# tech_safari_data_logger.net
KiCad netlist of a schematic drawn in EAGLE
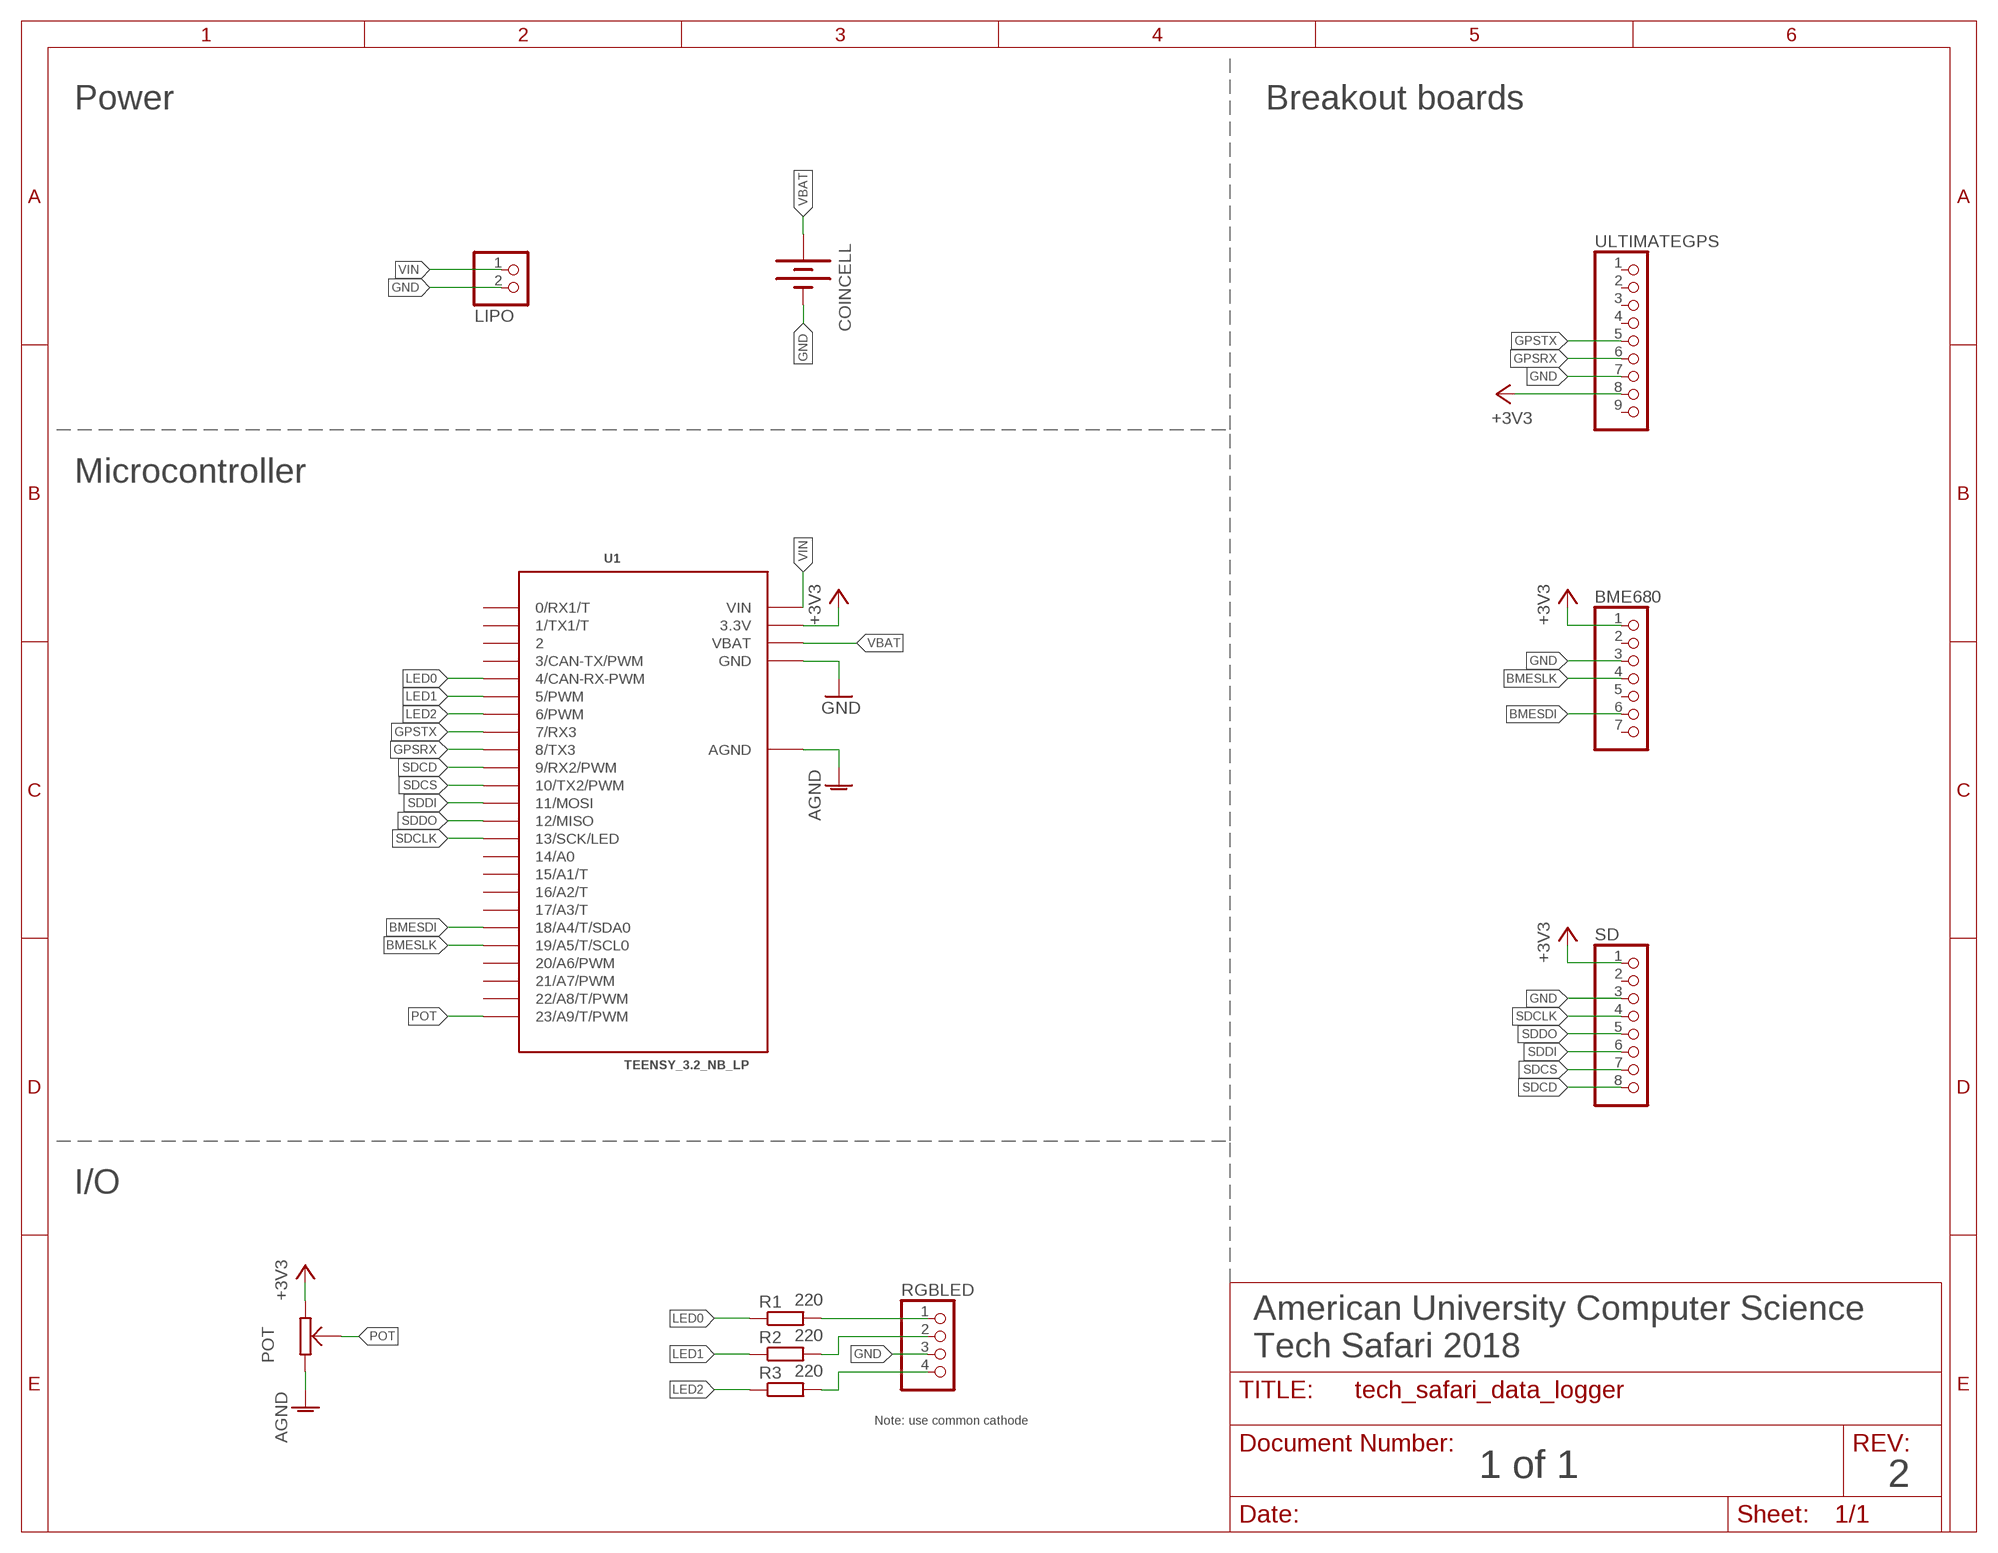
[diagram p0: schematic, sheet 1]

(export (version "E")
  (design (tool "Eeschema 10.0.6"))
  (components
    (comp (ref "BME680")
      (value "PINHD-1X7")
      (footprint "eagle-import:1X07")
      (libsource (lib "eagle-import") (part "PINHD-1X7"))
    )
    (comp (ref "COINCELL")
      (value "BATTERY")
      (footprint "eagle-import:BATTCON_20MM_SMALL")
      (libsource (lib "eagle-import") (part "BATTERY"))
    )
    (comp (ref "LIPO")
      (value "JST_2PIN-THM-RA")
      (footprint "eagle-import:JST-PH-2-THM-RA")
      (libsource (lib "eagle-import") (part "JST_2PIN-THM-RA"))
    )
    (comp (ref "POT")
      (value "POTENTIOMETER_THRU")
      (footprint "eagle-import:POTENTIOMETER_THRU")
      (libsource (lib "eagle-import") (part "POTENTIOMETER_THRU"))
    )
    (comp (ref "R1")
      (value "220")
      (footprint "eagle-import:0207_10")
      (libsource (lib "eagle-import") (part "R-EU_0207/10"))
    )
    (comp (ref "R2")
      (value "220")
      (footprint "eagle-import:0207_10")
      (libsource (lib "eagle-import") (part "R-EU_0207/10"))
    )
    (comp (ref "R3")
      (value "220")
      (footprint "eagle-import:0207_10")
      (libsource (lib "eagle-import") (part "R-EU_0207/10"))
    )
    (comp (ref "RGBLED")
      (value "PINHD-1X4")
      (footprint "eagle-import:1X04")
      (libsource (lib "eagle-import") (part "PINHD-1X4"))
    )
    (comp (ref "SD")
      (value "PINHD-1X8")
      (footprint "eagle-import:1X08")
      (libsource (lib "eagle-import") (part "PINHD-1X8"))
    )
    (comp (ref "U1")
      (value "TEENSY_3.2_NB_LP")
      (footprint "eagle-import:TEENSY_3.2__NB_LP")
      (libsource (lib "eagle-import") (part "TEENSY_3.2_NB_LP"))
    )
    (comp (ref "ULTIMATEGPS")
      (value "PINHD-1X9")
      (footprint "eagle-import:1X09")
      (libsource (lib "eagle-import") (part "PINHD-1X9"))
    )
  )
  (nets
    (net (code "1") (name "+3V3") (class "Default")
      (node (ref "BME680") (pin "1") (pinfunction "1_1") (pintype "passive"))
      (node (ref "POT") (pin "3") (pinfunction "3_3") (pintype "passive"))
      (node (ref "SD") (pin "1") (pinfunction "1_1") (pintype "passive"))
      (node (ref "U1") (pin "3.3V") (pinfunction "3.3V_3.3V") (pintype "power_in"))
      (node (ref "ULTIMATEGPS") (pin "8") (pinfunction "8_8") (pintype "passive"))
    )
    (net (code "2") (name "AGND") (class "Default")
      (node (ref "POT") (pin "1") (pinfunction "1_1") (pintype "passive"))
      (node (ref "U1") (pin "AGND") (pinfunction "AGND_AGND") (pintype "power_in"))
    )
    (net (code "3") (name "BMESDI") (class "Default")
      (node (ref "BME680") (pin "6") (pinfunction "6_6") (pintype "passive"))
      (node (ref "U1") (pin "18/A4") (pinfunction "18/A4/T/SDA0_18/A4") (pintype "bidirectional"))
    )
    (net (code "4") (name "BMESLK") (class "Default")
      (node (ref "BME680") (pin "4") (pinfunction "4_4") (pintype "passive"))
      (node (ref "U1") (pin "19/A5") (pinfunction "19/A5/T/SCL0_19/A5") (pintype "bidirectional"))
    )
    (net (code "5") (name "GND") (class "Default")
      (node (ref "BME680") (pin "3") (pinfunction "3_3") (pintype "passive"))
      (node (ref "COINCELL") (pin "NEG") (pinfunction "-_NEG") (pintype "power_in"))
      (node (ref "LIPO") (pin "2") (pinfunction "1_2") (pintype "passive"))
      (node (ref "RGBLED") (pin "3") (pinfunction "3_3") (pintype "passive"))
      (node (ref "SD") (pin "3") (pinfunction "3_3") (pintype "passive"))
      (node (ref "U1") (pin "GND") (pinfunction "GND_GND") (pintype "power_in"))
      (node (ref "ULTIMATEGPS") (pin "7") (pinfunction "7_7") (pintype "passive"))
    )
    (net (code "6") (name "GPSRX") (class "Default")
      (node (ref "U1") (pin "8") (pinfunction "8/TX3_8") (pintype "bidirectional"))
      (node (ref "ULTIMATEGPS") (pin "6") (pinfunction "6_6") (pintype "passive"))
    )
    (net (code "7") (name "GPSTX") (class "Default")
      (node (ref "U1") (pin "7") (pinfunction "7/RX3_7") (pintype "bidirectional"))
      (node (ref "ULTIMATEGPS") (pin "5") (pinfunction "5_5") (pintype "passive"))
    )
    (net (code "8") (name "LED0") (class "Default")
      (node (ref "R1") (pin "1") (pinfunction "1_1") (pintype "passive"))
      (node (ref "U1") (pin "4") (pinfunction "4/CAN-RX-PWM_4") (pintype "bidirectional"))
    )
    (net (code "9") (name "LED1") (class "Default")
      (node (ref "R2") (pin "1") (pinfunction "1_1") (pintype "passive"))
      (node (ref "U1") (pin "5") (pinfunction "5/PWM_5") (pintype "bidirectional"))
    )
    (net (code "10") (name "LED2") (class "Default")
      (node (ref "R3") (pin "1") (pinfunction "1_1") (pintype "passive"))
      (node (ref "U1") (pin "6") (pinfunction "6/PWM_6") (pintype "bidirectional"))
    )
    (net (code "11") (name "Net-(R1-Pad2)") (class "Default")
      (node (ref "R1") (pin "2") (pinfunction "2_2") (pintype "passive"))
      (node (ref "RGBLED") (pin "1") (pinfunction "1_1") (pintype "passive"))
    )
    (net (code "12") (name "Net-(R2-Pad2)") (class "Default")
      (node (ref "R2") (pin "2") (pinfunction "2_2") (pintype "passive"))
      (node (ref "RGBLED") (pin "2") (pinfunction "2_2") (pintype "passive"))
    )
    (net (code "13") (name "Net-(R3-Pad2)") (class "Default")
      (node (ref "R3") (pin "2") (pinfunction "2_2") (pintype "passive"))
      (node (ref "RGBLED") (pin "4") (pinfunction "4_4") (pintype "passive"))
    )
    (net (code "14") (name "POT") (class "Default")
      (node (ref "POT") (pin "2") (pinfunction "2_2") (pintype "passive"))
      (node (ref "U1") (pin "23/A9") (pinfunction "23/A9/T/PWM_23/A9") (pintype "bidirectional"))
    )
    (net (code "15") (name "SDCD") (class "Default")
      (node (ref "SD") (pin "8") (pinfunction "8_8") (pintype "passive"))
      (node (ref "U1") (pin "9") (pinfunction "9/RX2/PWM_9") (pintype "bidirectional"))
    )
    (net (code "16") (name "SDCLK") (class "Default")
      (node (ref "SD") (pin "4") (pinfunction "4_4") (pintype "passive"))
      (node (ref "U1") (pin "13") (pinfunction "13/SCK/LED_13") (pintype "bidirectional"))
    )
    (net (code "17") (name "SDCS") (class "Default")
      (node (ref "SD") (pin "7") (pinfunction "7_7") (pintype "passive"))
      (node (ref "U1") (pin "10") (pinfunction "10/TX2/PWM_10") (pintype "bidirectional"))
    )
    (net (code "18") (name "SDDI") (class "Default")
      (node (ref "SD") (pin "6") (pinfunction "6_6") (pintype "passive"))
      (node (ref "U1") (pin "11") (pinfunction "11/MOSI_11") (pintype "bidirectional"))
    )
    (net (code "19") (name "SDDO") (class "Default")
      (node (ref "SD") (pin "5") (pinfunction "5_5") (pintype "passive"))
      (node (ref "U1") (pin "12") (pinfunction "12/MISO_12") (pintype "bidirectional"))
    )
    (net (code "20") (name "VBAT") (class "Default")
      (node (ref "COINCELL") (pin "1") (pinfunction "+_1") (pintype "power_in"))
      (node (ref "COINCELL") (pin "2") (pinfunction "+_2") (pintype "power_in"))
      (node (ref "COINCELL") (pin "3") (pinfunction "+_3") (pintype "power_in"))
      (node (ref "COINCELL") (pin "4") (pinfunction "+_4") (pintype "power_in"))
      (node (ref "U1") (pin "VBAT") (pinfunction "VBAT_VBAT") (pintype "power_in"))
    )
    (net (code "21") (name "VIN") (class "Default")
      (node (ref "LIPO") (pin "1") (pinfunction "2_1") (pintype "passive"))
      (node (ref "U1") (pin "VIN") (pinfunction "VIN_VIN") (pintype "power_in"))
    )
    (net (code "22") (name "unconnected-(BME680-Pad2)") (class "Default")
      (node (ref "BME680") (pin "2") (pinfunction "2_2") (pintype "passive"))
    )
    (net (code "23") (name "unconnected-(BME680-Pad5)") (class "Default")
      (node (ref "BME680") (pin "5") (pinfunction "5_5") (pintype "passive"))
    )
    (net (code "24") (name "unconnected-(BME680-Pad7)") (class "Default")
      (node (ref "BME680") (pin "7") (pinfunction "7_7") (pintype "passive"))
    )
    (net (code "25") (name "unconnected-(SD-Pad2)") (class "Default")
      (node (ref "SD") (pin "2") (pinfunction "2_2") (pintype "passive"))
    )
    (net (code "26") (name "unconnected-(U1-0{slash}RX1{slash}T-Pad0)") (class "Default")
      (node (ref "U1") (pin "0") (pinfunction "0/RX1/T_0") (pintype "bidirectional"))
    )
    (net (code "27") (name "unconnected-(U1-1{slash}TX1{slash}T-Pad1)") (class "Default")
      (node (ref "U1") (pin "1") (pinfunction "1/TX1/T_1") (pintype "bidirectional"))
    )
    (net (code "28") (name "unconnected-(U1-3{slash}CAN-TX{slash}PWM-Pad3)") (class "Default")
      (node (ref "U1") (pin "3") (pinfunction "3/CAN-TX/PWM_3") (pintype "bidirectional"))
    )
    (net (code "29") (name "unconnected-(U1-15{slash}A1{slash}T-Pad15{slash}A1)") (class "Default")
      (node (ref "U1") (pin "15/A1") (pinfunction "15/A1/T_15/A1") (pintype "bidirectional"))
    )
    (net (code "30") (name "unconnected-(U1-16{slash}A2{slash}T-Pad16{slash}A2)") (class "Default")
      (node (ref "U1") (pin "16/A2") (pinfunction "16/A2/T_16/A2") (pintype "bidirectional"))
    )
    (net (code "31") (name "unconnected-(U1-17{slash}A3{slash}T-Pad17{slash}A3)") (class "Default")
      (node (ref "U1") (pin "17/A3") (pinfunction "17/A3/T_17/A3") (pintype "bidirectional"))
    )
    (net (code "32") (name "unconnected-(U1-20{slash}A6{slash}PWM-Pad20{slash}A6)") (class "Default")
      (node (ref "U1") (pin "20/A6") (pinfunction "20/A6/PWM_20/A6") (pintype "bidirectional"))
    )
    (net (code "33") (name "unconnected-(U1-21{slash}A7{slash}PWM-Pad21{slash}A7)") (class "Default")
      (node (ref "U1") (pin "21/A7") (pinfunction "21/A7/PWM_21/A7") (pintype "bidirectional"))
    )
    (net (code "34") (name "unconnected-(U1-22{slash}A8{slash}T{slash}PWM-Pad22{slash}A8)") (class "Default")
      (node (ref "U1") (pin "22/A8") (pinfunction "22/A8/T/PWM_22/A8") (pintype "bidirectional"))
    )
    (net (code "35") (name "unconnected-(U1-Pad2)") (class "Default")
      (node (ref "U1") (pin "2") (pinfunction "2_2") (pintype "bidirectional"))
    )
    (net (code "36") (name "unconnected-(U1-Pad14{slash}A0)") (class "Default")
      (node (ref "U1") (pin "14/A0") (pinfunction "14/A0_14/A0") (pintype "bidirectional"))
    )
    (net (code "37") (name "unconnected-(ULTIMATEGPS-Pad1)") (class "Default")
      (node (ref "ULTIMATEGPS") (pin "1") (pinfunction "1_1") (pintype "passive"))
    )
    (net (code "38") (name "unconnected-(ULTIMATEGPS-Pad2)") (class "Default")
      (node (ref "ULTIMATEGPS") (pin "2") (pinfunction "2_2") (pintype "passive"))
    )
    (net (code "39") (name "unconnected-(ULTIMATEGPS-Pad3)") (class "Default")
      (node (ref "ULTIMATEGPS") (pin "3") (pinfunction "3_3") (pintype "passive"))
    )
    (net (code "40") (name "unconnected-(ULTIMATEGPS-Pad4)") (class "Default")
      (node (ref "ULTIMATEGPS") (pin "4") (pinfunction "4_4") (pintype "passive"))
    )
    (net (code "41") (name "unconnected-(ULTIMATEGPS-Pad9)") (class "Default")
      (node (ref "ULTIMATEGPS") (pin "9") (pinfunction "9_9") (pintype "passive"))
    )
  )
)
